# Aladdin_Lamp.net
KiCad netlist of a schematic drawn in EAGLE
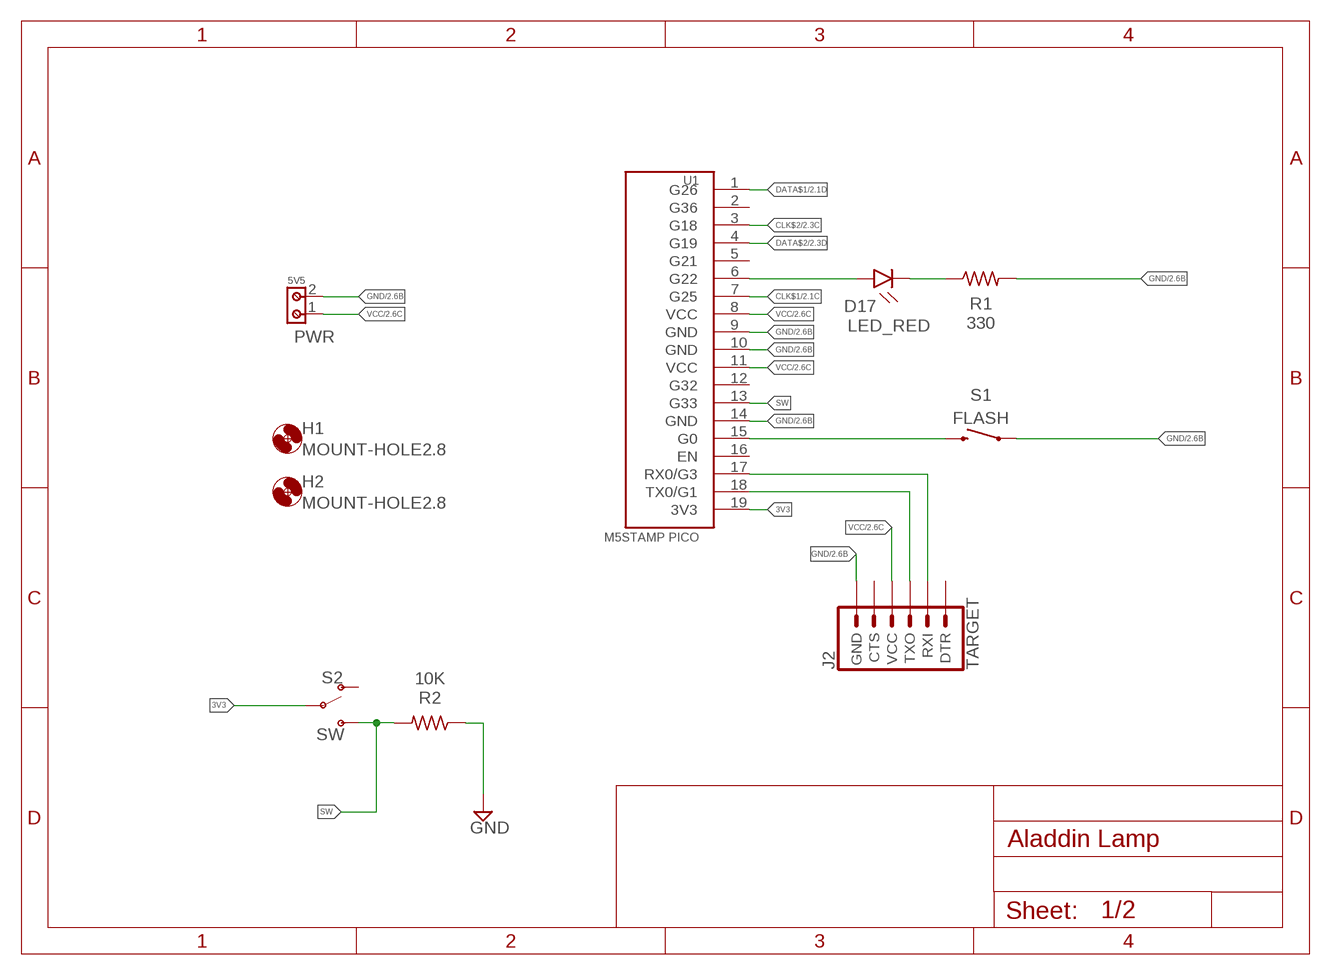
[diagram p0: schematic, sheet 1]
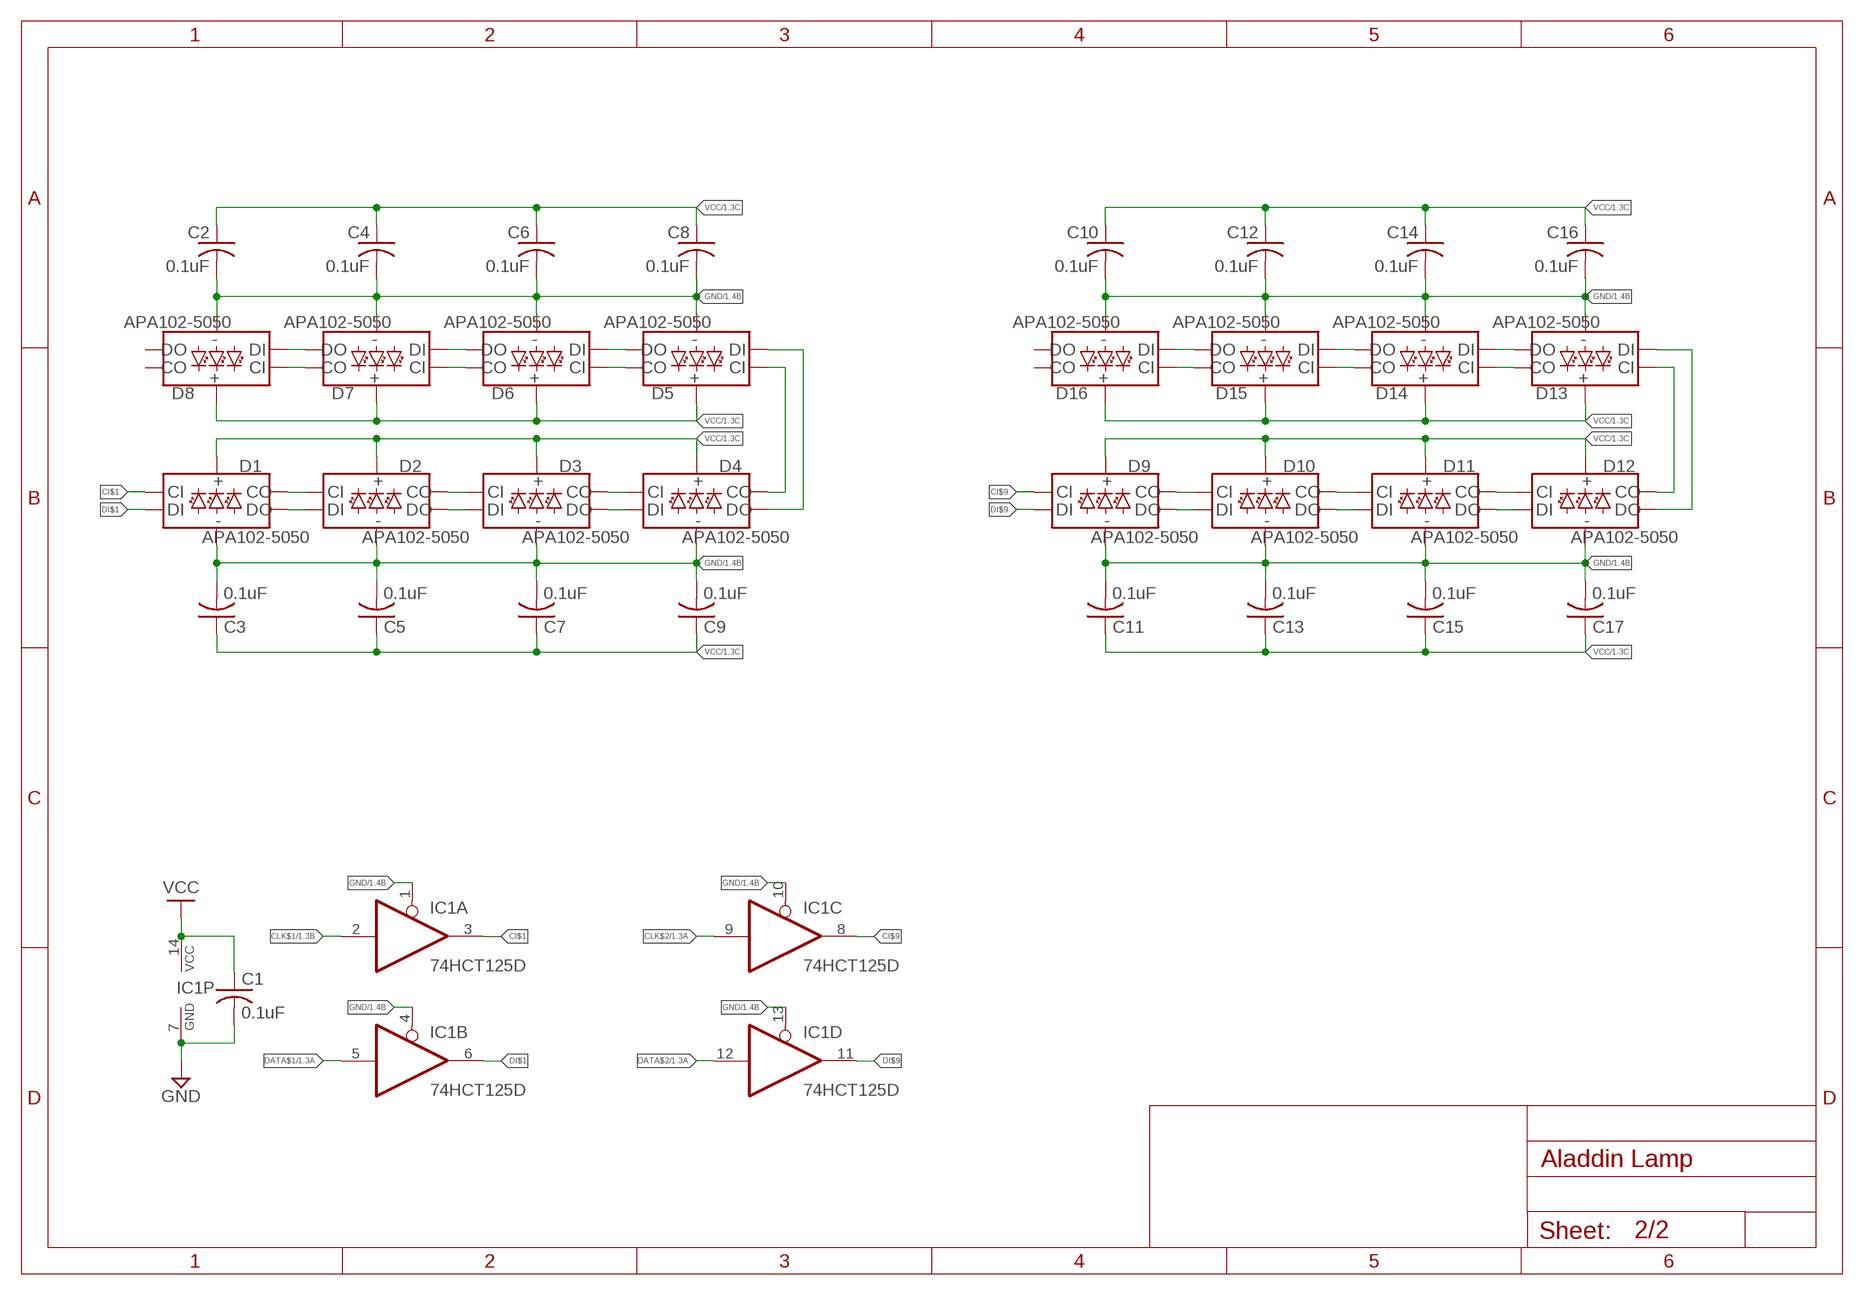
[diagram p1: schematic, sheet 2]

(export (version "E")
  (design (tool "Eeschema 10.0.6"))
  (components
    (comp (ref "D17")
      (value "LED_RED")
      (footprint "eagle-import:LEDC2012X110N_FLAT-R")
      (libsource (lib "eagle-import") (part "CHIP-FLAT-R_0805"))
    )
    (comp (ref "H1")
      (value "MOUNT-HOLE2.8")
      (footprint "eagle-import:2,8")
      (libsource (lib "eagle-import") (part "MOUNT-HOLE2.8"))
    )
    (comp (ref "H2")
      (value "MOUNT-HOLE2.8")
      (footprint "eagle-import:2,8")
      (libsource (lib "eagle-import") (part "MOUNT-HOLE2.8"))
    )
    (comp (ref "J2")
      (value "TARGET")
      (footprint "eagle-import:6_PIN_SERIAL_TARGET_SIDE_W_SILK")
      (libsource (lib "eagle-import") (part "6_PIN_SERIAL_TARGETSILK"))
    )
    (comp (ref "PWR")
      (value "5V5")
      (footprint "eagle-import:691213510002")
      (libsource (lib "eagle-import") (part "691213510002"))
    )
    (comp (ref "R1")
      (value "330")
      (footprint "eagle-import:RESC2012X65")
      (libsource (lib "eagle-import") (part "R-USCHIP-0805(2012-METRIC)_"))
    )
    (comp (ref "R2")
      (value "10K")
      (footprint "eagle-import:RESC2012X65")
      (libsource (lib "eagle-import") (part "R-USCHIP-0805(2012-METRIC)_"))
    )
    (comp (ref "S1")
      (value "FLASH")
      (footprint "eagle-import:TACTILE_SWITCH_SMD_5.2MM")
      (libsource (lib "eagle-import") (part "MOMENTARY-SWITCH-SPST-SMD-5.2MM"))
    )
    (comp (ref "S2")
      (value "SW")
      (footprint "eagle-import:SWITCH_SPST_SMD_A")
      (libsource (lib "eagle-import") (part "SWITCH-SPDT-SMD-RIGHT-ANGLE"))
    )
    (comp (ref "U1")
      (value "M5STAMP PICO")
      (footprint "eagle-import:M5STAMP-PICO")
      (libsource (lib "eagle-import") (part "M5STAMP-PICO"))
    )
    (comp (ref "C1")
      (value "0.1uF")
      (footprint "eagle-import:CAPC2012X110")
      (libsource (lib "eagle-import") (part "C-USCHIP-0805(2012-METRIC)_"))
    )
    (comp (ref "C2")
      (value "0.1uF")
      (footprint "eagle-import:CAPC2012X110")
      (libsource (lib "eagle-import") (part "C-USCHIP-0805(2012-METRIC)_"))
    )
    (comp (ref "C3")
      (value "0.1uF")
      (footprint "eagle-import:CAPC2012X110")
      (libsource (lib "eagle-import") (part "C-USCHIP-0805(2012-METRIC)_"))
    )
    (comp (ref "C4")
      (value "0.1uF")
      (footprint "eagle-import:CAPC2012X110")
      (libsource (lib "eagle-import") (part "C-USCHIP-0805(2012-METRIC)_"))
    )
    (comp (ref "C5")
      (value "0.1uF")
      (footprint "eagle-import:CAPC2012X110")
      (libsource (lib "eagle-import") (part "C-USCHIP-0805(2012-METRIC)_"))
    )
    (comp (ref "C6")
      (value "0.1uF")
      (footprint "eagle-import:CAPC2012X110")
      (libsource (lib "eagle-import") (part "C-USCHIP-0805(2012-METRIC)_"))
    )
    (comp (ref "C7")
      (value "0.1uF")
      (footprint "eagle-import:CAPC2012X110")
      (libsource (lib "eagle-import") (part "C-USCHIP-0805(2012-METRIC)_"))
    )
    (comp (ref "C8")
      (value "0.1uF")
      (footprint "eagle-import:CAPC2012X110")
      (libsource (lib "eagle-import") (part "C-USCHIP-0805(2012-METRIC)_"))
    )
    (comp (ref "C9")
      (value "0.1uF")
      (footprint "eagle-import:CAPC2012X110")
      (libsource (lib "eagle-import") (part "C-USCHIP-0805(2012-METRIC)_"))
    )
    (comp (ref "C10")
      (value "0.1uF")
      (footprint "eagle-import:CAPC2012X110")
      (libsource (lib "eagle-import") (part "C-USCHIP-0805(2012-METRIC)_"))
    )
    (comp (ref "C11")
      (value "0.1uF")
      (footprint "eagle-import:CAPC2012X110")
      (libsource (lib "eagle-import") (part "C-USCHIP-0805(2012-METRIC)_"))
    )
    (comp (ref "C12")
      (value "0.1uF")
      (footprint "eagle-import:CAPC2012X110")
      (libsource (lib "eagle-import") (part "C-USCHIP-0805(2012-METRIC)_"))
    )
    (comp (ref "C13")
      (value "0.1uF")
      (footprint "eagle-import:CAPC2012X110")
      (libsource (lib "eagle-import") (part "C-USCHIP-0805(2012-METRIC)_"))
    )
    (comp (ref "C14")
      (value "0.1uF")
      (footprint "eagle-import:CAPC2012X110")
      (libsource (lib "eagle-import") (part "C-USCHIP-0805(2012-METRIC)_"))
    )
    (comp (ref "C15")
      (value "0.1uF")
      (footprint "eagle-import:CAPC2012X110")
      (libsource (lib "eagle-import") (part "C-USCHIP-0805(2012-METRIC)_"))
    )
    (comp (ref "C16")
      (value "0.1uF")
      (footprint "eagle-import:CAPC2012X110")
      (libsource (lib "eagle-import") (part "C-USCHIP-0805(2012-METRIC)_"))
    )
    (comp (ref "C17")
      (value "0.1uF")
      (footprint "eagle-import:CAPC2012X110")
      (libsource (lib "eagle-import") (part "C-USCHIP-0805(2012-METRIC)_"))
    )
    (comp (ref "D1")
      (value "APA102-5050")
      (footprint "eagle-import:APA102-5050")
      (libsource (lib "eagle-import") (part "APA102-5050"))
    )
    (comp (ref "D2")
      (value "APA102-5050")
      (footprint "eagle-import:APA102-5050")
      (libsource (lib "eagle-import") (part "APA102-5050"))
    )
    (comp (ref "D3")
      (value "APA102-5050")
      (footprint "eagle-import:APA102-5050")
      (libsource (lib "eagle-import") (part "APA102-5050"))
    )
    (comp (ref "D4")
      (value "APA102-5050")
      (footprint "eagle-import:APA102-5050")
      (libsource (lib "eagle-import") (part "APA102-5050"))
    )
    (comp (ref "D5")
      (value "APA102-5050")
      (footprint "eagle-import:APA102-5050")
      (libsource (lib "eagle-import") (part "APA102-5050"))
    )
    (comp (ref "D6")
      (value "APA102-5050")
      (footprint "eagle-import:APA102-5050")
      (libsource (lib "eagle-import") (part "APA102-5050"))
    )
    (comp (ref "D7")
      (value "APA102-5050")
      (footprint "eagle-import:APA102-5050")
      (libsource (lib "eagle-import") (part "APA102-5050"))
    )
    (comp (ref "D8")
      (value "APA102-5050")
      (footprint "eagle-import:APA102-5050")
      (libsource (lib "eagle-import") (part "APA102-5050"))
    )
    (comp (ref "D9")
      (value "APA102-5050")
      (footprint "eagle-import:APA102-5050")
      (libsource (lib "eagle-import") (part "APA102-5050"))
    )
    (comp (ref "D10")
      (value "APA102-5050")
      (footprint "eagle-import:APA102-5050")
      (libsource (lib "eagle-import") (part "APA102-5050"))
    )
    (comp (ref "D11")
      (value "APA102-5050")
      (footprint "eagle-import:APA102-5050")
      (libsource (lib "eagle-import") (part "APA102-5050"))
    )
    (comp (ref "D12")
      (value "APA102-5050")
      (footprint "eagle-import:APA102-5050")
      (libsource (lib "eagle-import") (part "APA102-5050"))
    )
    (comp (ref "D13")
      (value "APA102-5050")
      (footprint "eagle-import:APA102-5050")
      (libsource (lib "eagle-import") (part "APA102-5050"))
    )
    (comp (ref "D14")
      (value "APA102-5050")
      (footprint "eagle-import:APA102-5050")
      (libsource (lib "eagle-import") (part "APA102-5050"))
    )
    (comp (ref "D15")
      (value "APA102-5050")
      (footprint "eagle-import:APA102-5050")
      (libsource (lib "eagle-import") (part "APA102-5050"))
    )
    (comp (ref "D16")
      (value "APA102-5050")
      (footprint "eagle-import:APA102-5050")
      (libsource (lib "eagle-import") (part "APA102-5050"))
    )
    (comp (ref "IC1")
      (value "74HCT125D")
      (footprint "eagle-import:SO14")
      (libsource (lib "eagle-import") (part "74125DHCT"))
    )
  )
  (nets
    (net (code "1") (name "3V3") (class "Default")
      (node (ref "S2") (pin "2") (pinfunction "P_2") (pintype "passive"))
      (node (ref "U1") (pin "19") (pinfunction "3V3_19") (pintype "power_in"))
    )
    (net (code "2") (name "CI$1") (class "Default")
      (node (ref "D1") (pin "P2") (pinfunction "CI_P2") (pintype "bidirectional"))
      (node (ref "IC1") (pin "3") (pinfunction "O_3") (pintype "tri_state"))
    )
    (net (code "3") (name "CI$9") (class "Default")
      (node (ref "D9") (pin "P2") (pinfunction "CI_P2") (pintype "bidirectional"))
      (node (ref "IC1") (pin "8") (pinfunction "O_8") (pintype "tri_state"))
    )
    (net (code "4") (name "CLK$1") (class "Default")
      (node (ref "IC1") (pin "2") (pinfunction "I_2") (pintype "input"))
      (node (ref "U1") (pin "7") (pinfunction "G25_7") (pintype "bidirectional"))
    )
    (net (code "5") (name "CLK$2") (class "Default")
      (node (ref "IC1") (pin "9") (pinfunction "I_9") (pintype "input"))
      (node (ref "U1") (pin "3") (pinfunction "G18_3") (pintype "bidirectional"))
    )
    (net (code "6") (name "DATA$1") (class "Default")
      (node (ref "IC1") (pin "5") (pinfunction "I_5") (pintype "input"))
      (node (ref "U1") (pin "1") (pinfunction "G26_1") (pintype "bidirectional"))
    )
    (net (code "7") (name "DATA$2") (class "Default")
      (node (ref "IC1") (pin "12") (pinfunction "I_12") (pintype "input"))
      (node (ref "U1") (pin "4") (pinfunction "G19_4") (pintype "bidirectional"))
    )
    (net (code "8") (name "DI$1") (class "Default")
      (node (ref "D1") (pin "P1") (pinfunction "DI_P1") (pintype "bidirectional"))
      (node (ref "IC1") (pin "6") (pinfunction "O_6") (pintype "tri_state"))
    )
    (net (code "9") (name "DI$9") (class "Default")
      (node (ref "D9") (pin "P1") (pinfunction "DI_P1") (pintype "bidirectional"))
      (node (ref "IC1") (pin "11") (pinfunction "O_11") (pintype "tri_state"))
    )
    (net (code "10") (name "GND") (class "Default")
      (node (ref "C1") (pin "2") (pinfunction "2_2") (pintype "passive"))
      (node (ref "C10") (pin "2") (pinfunction "2_2") (pintype "passive"))
      (node (ref "C11") (pin "2") (pinfunction "2_2") (pintype "passive"))
      (node (ref "C12") (pin "2") (pinfunction "2_2") (pintype "passive"))
      (node (ref "C13") (pin "2") (pinfunction "2_2") (pintype "passive"))
      (node (ref "C14") (pin "2") (pinfunction "2_2") (pintype "passive"))
      (node (ref "C15") (pin "2") (pinfunction "2_2") (pintype "passive"))
      (node (ref "C16") (pin "2") (pinfunction "2_2") (pintype "passive"))
      (node (ref "C17") (pin "2") (pinfunction "2_2") (pintype "passive"))
      (node (ref "C2") (pin "2") (pinfunction "2_2") (pintype "passive"))
      (node (ref "C3") (pin "2") (pinfunction "2_2") (pintype "passive"))
      (node (ref "C4") (pin "2") (pinfunction "2_2") (pintype "passive"))
      (node (ref "C5") (pin "2") (pinfunction "2_2") (pintype "passive"))
      (node (ref "C6") (pin "2") (pinfunction "2_2") (pintype "passive"))
      (node (ref "C7") (pin "2") (pinfunction "2_2") (pintype "passive"))
      (node (ref "C8") (pin "2") (pinfunction "2_2") (pintype "passive"))
      (node (ref "C9") (pin "2") (pinfunction "2_2") (pintype "passive"))
      (node (ref "D1") (pin "P3") (pinfunction "GND_P3") (pintype "bidirectional"))
      (node (ref "D10") (pin "P3") (pinfunction "GND_P3") (pintype "bidirectional"))
      (node (ref "D11") (pin "P3") (pinfunction "GND_P3") (pintype "bidirectional"))
      (node (ref "D12") (pin "P3") (pinfunction "GND_P3") (pintype "bidirectional"))
      (node (ref "D13") (pin "P3") (pinfunction "GND_P3") (pintype "bidirectional"))
      (node (ref "D14") (pin "P3") (pinfunction "GND_P3") (pintype "bidirectional"))
      (node (ref "D15") (pin "P3") (pinfunction "GND_P3") (pintype "bidirectional"))
      (node (ref "D16") (pin "P3") (pinfunction "GND_P3") (pintype "bidirectional"))
      (node (ref "D2") (pin "P3") (pinfunction "GND_P3") (pintype "bidirectional"))
      (node (ref "D3") (pin "P3") (pinfunction "GND_P3") (pintype "bidirectional"))
      (node (ref "D4") (pin "P3") (pinfunction "GND_P3") (pintype "bidirectional"))
      (node (ref "D5") (pin "P3") (pinfunction "GND_P3") (pintype "bidirectional"))
      (node (ref "D6") (pin "P3") (pinfunction "GND_P3") (pintype "bidirectional"))
      (node (ref "D7") (pin "P3") (pinfunction "GND_P3") (pintype "bidirectional"))
      (node (ref "D8") (pin "P3") (pinfunction "GND_P3") (pintype "bidirectional"))
      (node (ref "D9") (pin "P3") (pinfunction "GND_P3") (pintype "bidirectional"))
      (node (ref "IC1") (pin "1") (pinfunction "OE_1") (pintype "input"))
      (node (ref "IC1") (pin "10") (pinfunction "OE_10") (pintype "input"))
      (node (ref "IC1") (pin "13") (pinfunction "OE_13") (pintype "input"))
      (node (ref "IC1") (pin "4") (pinfunction "OE_4") (pintype "input"))
      (node (ref "IC1") (pin "7") (pinfunction "GND_7") (pintype "power_in"))
      (node (ref "J2") (pin "P$6") (pinfunction "GND_P$6") (pintype "passive"))
      (node (ref "PWR") (pin "2") (pinfunction "2_2") (pintype "passive"))
      (node (ref "R1") (pin "2") (pinfunction "2_2") (pintype "passive"))
      (node (ref "R2") (pin "1") (pinfunction "1_1") (pintype "passive"))
      (node (ref "S1") (pin "1") (pinfunction "1_1") (pintype "passive"))
      (node (ref "U1") (pin "10") (pinfunction "GND_10") (pintype "power_in"))
      (node (ref "U1") (pin "14") (pinfunction "GND_14") (pintype "power_in"))
      (node (ref "U1") (pin "9") (pinfunction "GND_9") (pintype "power_in"))
    )
    (net (code "11") (name "Net-(D1-CO)") (class "Default")
      (node (ref "D1") (pin "P5") (pinfunction "CO_P5") (pintype "bidirectional"))
      (node (ref "D2") (pin "P2") (pinfunction "CI_P2") (pintype "bidirectional"))
    )
    (net (code "12") (name "Net-(D1-DO)") (class "Default")
      (node (ref "D1") (pin "P6") (pinfunction "DO_P6") (pintype "bidirectional"))
      (node (ref "D2") (pin "P1") (pinfunction "DI_P1") (pintype "bidirectional"))
    )
    (net (code "13") (name "Net-(D2-CO)") (class "Default")
      (node (ref "D2") (pin "P5") (pinfunction "CO_P5") (pintype "bidirectional"))
      (node (ref "D3") (pin "P2") (pinfunction "CI_P2") (pintype "bidirectional"))
    )
    (net (code "14") (name "Net-(D2-DO)") (class "Default")
      (node (ref "D2") (pin "P6") (pinfunction "DO_P6") (pintype "bidirectional"))
      (node (ref "D3") (pin "P1") (pinfunction "DI_P1") (pintype "bidirectional"))
    )
    (net (code "15") (name "Net-(D3-CO)") (class "Default")
      (node (ref "D3") (pin "P5") (pinfunction "CO_P5") (pintype "bidirectional"))
      (node (ref "D4") (pin "P2") (pinfunction "CI_P2") (pintype "bidirectional"))
    )
    (net (code "16") (name "Net-(D3-DO)") (class "Default")
      (node (ref "D3") (pin "P6") (pinfunction "DO_P6") (pintype "bidirectional"))
      (node (ref "D4") (pin "P1") (pinfunction "DI_P1") (pintype "bidirectional"))
    )
    (net (code "17") (name "Net-(D4-CO)") (class "Default")
      (node (ref "D4") (pin "P5") (pinfunction "CO_P5") (pintype "bidirectional"))
      (node (ref "D5") (pin "P2") (pinfunction "CI_P2") (pintype "bidirectional"))
    )
    (net (code "18") (name "Net-(D4-DO)") (class "Default")
      (node (ref "D4") (pin "P6") (pinfunction "DO_P6") (pintype "bidirectional"))
      (node (ref "D5") (pin "P1") (pinfunction "DI_P1") (pintype "bidirectional"))
    )
    (net (code "19") (name "Net-(D5-CO)") (class "Default")
      (node (ref "D5") (pin "P5") (pinfunction "CO_P5") (pintype "bidirectional"))
      (node (ref "D6") (pin "P2") (pinfunction "CI_P2") (pintype "bidirectional"))
    )
    (net (code "20") (name "Net-(D5-DO)") (class "Default")
      (node (ref "D5") (pin "P6") (pinfunction "DO_P6") (pintype "bidirectional"))
      (node (ref "D6") (pin "P1") (pinfunction "DI_P1") (pintype "bidirectional"))
    )
    (net (code "21") (name "Net-(D6-CO)") (class "Default")
      (node (ref "D6") (pin "P5") (pinfunction "CO_P5") (pintype "bidirectional"))
      (node (ref "D7") (pin "P2") (pinfunction "CI_P2") (pintype "bidirectional"))
    )
    (net (code "22") (name "Net-(D6-DO)") (class "Default")
      (node (ref "D6") (pin "P6") (pinfunction "DO_P6") (pintype "bidirectional"))
      (node (ref "D7") (pin "P1") (pinfunction "DI_P1") (pintype "bidirectional"))
    )
    (net (code "23") (name "Net-(D7-CO)") (class "Default")
      (node (ref "D7") (pin "P5") (pinfunction "CO_P5") (pintype "bidirectional"))
      (node (ref "D8") (pin "P2") (pinfunction "CI_P2") (pintype "bidirectional"))
    )
    (net (code "24") (name "Net-(D7-DO)") (class "Default")
      (node (ref "D7") (pin "P6") (pinfunction "DO_P6") (pintype "bidirectional"))
      (node (ref "D8") (pin "P1") (pinfunction "DI_P1") (pintype "bidirectional"))
    )
    (net (code "25") (name "Net-(D10-CI)") (class "Default")
      (node (ref "D10") (pin "P2") (pinfunction "CI_P2") (pintype "bidirectional"))
      (node (ref "D9") (pin "P5") (pinfunction "CO_P5") (pintype "bidirectional"))
    )
    (net (code "26") (name "Net-(D10-CO)") (class "Default")
      (node (ref "D10") (pin "P5") (pinfunction "CO_P5") (pintype "bidirectional"))
      (node (ref "D11") (pin "P2") (pinfunction "CI_P2") (pintype "bidirectional"))
    )
    (net (code "27") (name "Net-(D10-DI)") (class "Default")
      (node (ref "D10") (pin "P1") (pinfunction "DI_P1") (pintype "bidirectional"))
      (node (ref "D9") (pin "P6") (pinfunction "DO_P6") (pintype "bidirectional"))
    )
    (net (code "28") (name "Net-(D10-DO)") (class "Default")
      (node (ref "D10") (pin "P6") (pinfunction "DO_P6") (pintype "bidirectional"))
      (node (ref "D11") (pin "P1") (pinfunction "DI_P1") (pintype "bidirectional"))
    )
    (net (code "29") (name "Net-(D11-CO)") (class "Default")
      (node (ref "D11") (pin "P5") (pinfunction "CO_P5") (pintype "bidirectional"))
      (node (ref "D12") (pin "P2") (pinfunction "CI_P2") (pintype "bidirectional"))
    )
    (net (code "30") (name "Net-(D11-DO)") (class "Default")
      (node (ref "D11") (pin "P6") (pinfunction "DO_P6") (pintype "bidirectional"))
      (node (ref "D12") (pin "P1") (pinfunction "DI_P1") (pintype "bidirectional"))
    )
    (net (code "31") (name "Net-(D12-CO)") (class "Default")
      (node (ref "D12") (pin "P5") (pinfunction "CO_P5") (pintype "bidirectional"))
      (node (ref "D13") (pin "P2") (pinfunction "CI_P2") (pintype "bidirectional"))
    )
    (net (code "32") (name "Net-(D12-DO)") (class "Default")
      (node (ref "D12") (pin "P6") (pinfunction "DO_P6") (pintype "bidirectional"))
      (node (ref "D13") (pin "P1") (pinfunction "DI_P1") (pintype "bidirectional"))
    )
    (net (code "33") (name "Net-(D13-CO)") (class "Default")
      (node (ref "D13") (pin "P5") (pinfunction "CO_P5") (pintype "bidirectional"))
      (node (ref "D14") (pin "P2") (pinfunction "CI_P2") (pintype "bidirectional"))
    )
    (net (code "34") (name "Net-(D13-DO)") (class "Default")
      (node (ref "D13") (pin "P6") (pinfunction "DO_P6") (pintype "bidirectional"))
      (node (ref "D14") (pin "P1") (pinfunction "DI_P1") (pintype "bidirectional"))
    )
    (net (code "35") (name "Net-(D14-CO)") (class "Default")
      (node (ref "D14") (pin "P5") (pinfunction "CO_P5") (pintype "bidirectional"))
      (node (ref "D15") (pin "P2") (pinfunction "CI_P2") (pintype "bidirectional"))
    )
    (net (code "36") (name "Net-(D14-DO)") (class "Default")
      (node (ref "D14") (pin "P6") (pinfunction "DO_P6") (pintype "bidirectional"))
      (node (ref "D15") (pin "P1") (pinfunction "DI_P1") (pintype "bidirectional"))
    )
    (net (code "37") (name "Net-(D15-CO)") (class "Default")
      (node (ref "D15") (pin "P5") (pinfunction "CO_P5") (pintype "bidirectional"))
      (node (ref "D16") (pin "P2") (pinfunction "CI_P2") (pintype "bidirectional"))
    )
    (net (code "38") (name "Net-(D15-DO)") (class "Default")
      (node (ref "D15") (pin "P6") (pinfunction "DO_P6") (pintype "bidirectional"))
      (node (ref "D16") (pin "P1") (pinfunction "DI_P1") (pintype "bidirectional"))
    )
    (net (code "39") (name "Net-(D17-PadC)") (class "Default")
      (node (ref "D17") (pin "C") (pinfunction "C_C") (pintype "passive"))
      (node (ref "R1") (pin "1") (pinfunction "1_1") (pintype "passive"))
    )
    (net (code "40") (name "Net-(J2-RXI)") (class "Default")
      (node (ref "J2") (pin "P$3") (pinfunction "RXI_P$3") (pintype "passive"))
      (node (ref "U1") (pin "17") (pinfunction "RX0/G3_17") (pintype "bidirectional"))
    )
    (net (code "41") (name "Net-(J2-TXO)") (class "Default")
      (node (ref "J2") (pin "P$2") (pinfunction "TXO_P$2") (pintype "passive"))
      (node (ref "U1") (pin "18") (pinfunction "TX0/G1_18") (pintype "bidirectional"))
    )
    (net (code "42") (name "Net-(S1-2)") (class "Default")
      (node (ref "S1") (pin "3") (pinfunction "2_3") (pintype "passive"))
      (node (ref "U1") (pin "15") (pinfunction "G0_15") (pintype "bidirectional"))
    )
    (net (code "43") (name "Net-(U1-G22)") (class "Default")
      (node (ref "D17") (pin "A") (pinfunction "A_A") (pintype "passive"))
      (node (ref "U1") (pin "6") (pinfunction "G22_6") (pintype "bidirectional"))
    )
    (net (code "44") (name "SW") (class "Default")
      (node (ref "R2") (pin "2") (pinfunction "2_2") (pintype "passive"))
      (node (ref "S2") (pin "3") (pinfunction "S_3") (pintype "passive"))
      (node (ref "U1") (pin "13") (pinfunction "G33_13") (pintype "bidirectional"))
    )
    (net (code "45") (name "VCC") (class "Default")
      (node (ref "C1") (pin "1") (pinfunction "1_1") (pintype "passive"))
      (node (ref "C10") (pin "1") (pinfunction "1_1") (pintype "passive"))
      (node (ref "C11") (pin "1") (pinfunction "1_1") (pintype "passive"))
      (node (ref "C12") (pin "1") (pinfunction "1_1") (pintype "passive"))
      (node (ref "C13") (pin "1") (pinfunction "1_1") (pintype "passive"))
      (node (ref "C14") (pin "1") (pinfunction "1_1") (pintype "passive"))
      (node (ref "C15") (pin "1") (pinfunction "1_1") (pintype "passive"))
      (node (ref "C16") (pin "1") (pinfunction "1_1") (pintype "passive"))
      (node (ref "C17") (pin "1") (pinfunction "1_1") (pintype "passive"))
      (node (ref "C2") (pin "1") (pinfunction "1_1") (pintype "passive"))
      (node (ref "C3") (pin "1") (pinfunction "1_1") (pintype "passive"))
      (node (ref "C4") (pin "1") (pinfunction "1_1") (pintype "passive"))
      (node (ref "C5") (pin "1") (pinfunction "1_1") (pintype "passive"))
      (node (ref "C6") (pin "1") (pinfunction "1_1") (pintype "passive"))
      (node (ref "C7") (pin "1") (pinfunction "1_1") (pintype "passive"))
      (node (ref "C8") (pin "1") (pinfunction "1_1") (pintype "passive"))
      (node (ref "C9") (pin "1") (pinfunction "1_1") (pintype "passive"))
      (node (ref "D1") (pin "P4") (pinfunction "VCC_P4") (pintype "bidirectional"))
      (node (ref "D10") (pin "P4") (pinfunction "VCC_P4") (pintype "bidirectional"))
      (node (ref "D11") (pin "P4") (pinfunction "VCC_P4") (pintype "bidirectional"))
      (node (ref "D12") (pin "P4") (pinfunction "VCC_P4") (pintype "bidirectional"))
      (node (ref "D13") (pin "P4") (pinfunction "VCC_P4") (pintype "bidirectional"))
      (node (ref "D14") (pin "P4") (pinfunction "VCC_P4") (pintype "bidirectional"))
      (node (ref "D15") (pin "P4") (pinfunction "VCC_P4") (pintype "bidirectional"))
      (node (ref "D16") (pin "P4") (pinfunction "VCC_P4") (pintype "bidirectional"))
      (node (ref "D2") (pin "P4") (pinfunction "VCC_P4") (pintype "bidirectional"))
      (node (ref "D3") (pin "P4") (pinfunction "VCC_P4") (pintype "bidirectional"))
      (node (ref "D4") (pin "P4") (pinfunction "VCC_P4") (pintype "bidirectional"))
      (node (ref "D5") (pin "P4") (pinfunction "VCC_P4") (pintype "bidirectional"))
      (node (ref "D6") (pin "P4") (pinfunction "VCC_P4") (pintype "bidirectional"))
      (node (ref "D7") (pin "P4") (pinfunction "VCC_P4") (pintype "bidirectional"))
      (node (ref "D8") (pin "P4") (pinfunction "VCC_P4") (pintype "bidirectional"))
      (node (ref "D9") (pin "P4") (pinfunction "VCC_P4") (pintype "bidirectional"))
      (node (ref "IC1") (pin "14") (pinfunction "VCC_14") (pintype "power_in"))
      (node (ref "J2") (pin "P$4") (pinfunction "VCC_P$4") (pintype "passive"))
      (node (ref "PWR") (pin "1") (pinfunction "1_1") (pintype "passive"))
      (node (ref "U1") (pin "11") (pinfunction "VCC_11") (pintype "power_in"))
      (node (ref "U1") (pin "8") (pinfunction "VCC_8") (pintype "power_in"))
    )
    (net (code "46") (name "unconnected-(D8-CO-PadP5)") (class "Default")
      (node (ref "D8") (pin "P5") (pinfunction "CO_P5") (pintype "bidirectional"))
    )
    (net (code "47") (name "unconnected-(D8-DO-PadP6)") (class "Default")
      (node (ref "D8") (pin "P6") (pinfunction "DO_P6") (pintype "bidirectional"))
    )
    (net (code "48") (name "unconnected-(D16-CO-PadP5)") (class "Default")
      (node (ref "D16") (pin "P5") (pinfunction "CO_P5") (pintype "bidirectional"))
    )
    (net (code "49") (name "unconnected-(D16-DO-PadP6)") (class "Default")
      (node (ref "D16") (pin "P6") (pinfunction "DO_P6") (pintype "bidirectional"))
    )
    (net (code "50") (name "unconnected-(J2-CTS-PadP$5)") (class "Default")
      (node (ref "J2") (pin "P$5") (pinfunction "CTS_P$5") (pintype "passive"))
    )
    (net (code "51") (name "unconnected-(J2-DTR-PadP$1)") (class "Default")
      (node (ref "J2") (pin "P$1") (pinfunction "DTR_P$1") (pintype "passive"))
    )
    (net (code "52") (name "unconnected-(S2-O-Pad1)") (class "Default")
      (node (ref "S2") (pin "1") (pinfunction "O_1") (pintype "passive"))
    )
    (net (code "53") (name "unconnected-(U1-EN-Pad16)") (class "Default")
      (node (ref "U1") (pin "16") (pinfunction "EN_16") (pintype "passive"))
    )
    (net (code "54") (name "unconnected-(U1-G21-Pad5)") (class "Default")
      (node (ref "U1") (pin "5") (pinfunction "G21_5") (pintype "bidirectional"))
    )
    (net (code "55") (name "unconnected-(U1-G32-Pad12)") (class "Default")
      (node (ref "U1") (pin "12") (pinfunction "G32_12") (pintype "bidirectional"))
    )
    (net (code "56") (name "unconnected-(U1-G36-Pad2)") (class "Default")
      (node (ref "U1") (pin "2") (pinfunction "G36_2") (pintype "input"))
    )
  )
)
